# MAX31865.net
KiCad netlist of a schematic drawn in EAGLE
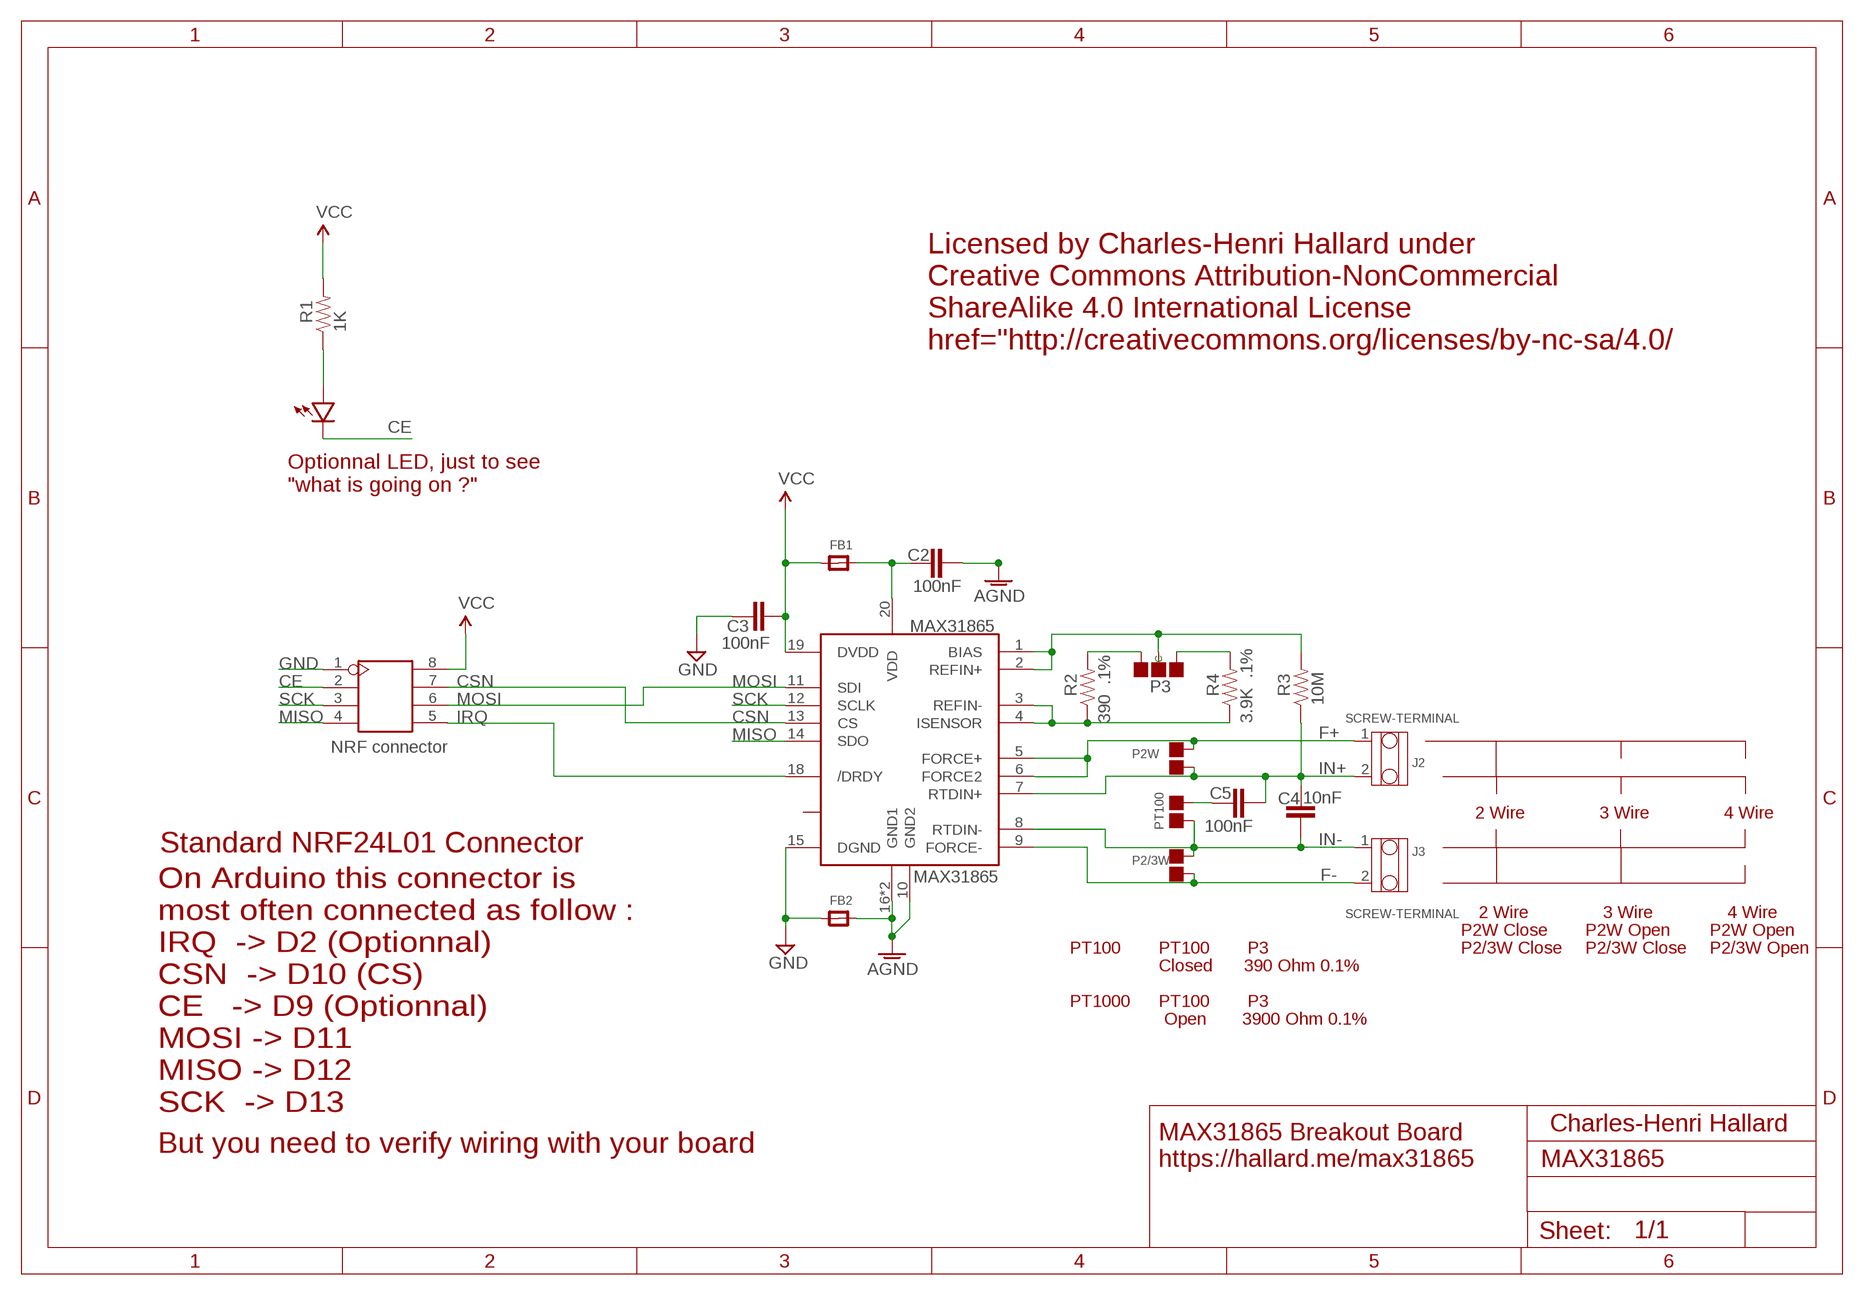
[diagram p0: schematic, sheet 1]

(export (version "E")
  (design (tool "Eeschema 10.0.6"))
  (components
    (comp (ref "C2")
      (value "100nF")
      (footprint "eagle-import:0603-CAP")
      (libsource (lib "eagle-import") (part "CAP0603-CAP"))
    )
    (comp (ref "C3")
      (value "100nF")
      (footprint "eagle-import:0603-CAP")
      (libsource (lib "eagle-import") (part "CAP0603-CAP"))
    )
    (comp (ref "C4")
      (value "10nF")
      (footprint "eagle-import:0603-CAP")
      (libsource (lib "eagle-import") (part "CAP0603-CAP"))
    )
    (comp (ref "C5")
      (value "100nF")
      (footprint "eagle-import:0603-CAP")
      (libsource (lib "eagle-import") (part "CAP0603-CAP"))
    )
    (comp (ref "FB1")
      (value "FERRITE_0603MP")
      (footprint "eagle-import:_0603MP")
      (libsource (lib "eagle-import") (part "FERRITE_0603MP"))
    )
    (comp (ref "FB2")
      (value "FERRITE_0603MP")
      (footprint "eagle-import:_0603MP")
      (libsource (lib "eagle-import") (part "FERRITE_0603MP"))
    )
    (comp (ref "J1")
      (value "NRF connector")
      (footprint "eagle-import:2X4P-2.54")
      (libsource (lib "eagle-import") (part "HEADER-2X4P-2.54"))
    )
    (comp (ref "J2")
      (value "SCREW-TERMINAL")
      (footprint "eagle-import:2P-3.5")
      (libsource (lib "eagle-import") (part "SCREW-TERMINAL-2P-3470070P1"))
    )
    (comp (ref "J3")
      (value "SCREW-TERMINAL")
      (footprint "eagle-import:2P-3.5")
      (libsource (lib "eagle-import") (part "SCREW-TERMINAL-2P-3470070P1"))
    )
    (comp (ref "MAX31865")
      (value "MAX31865")
      (footprint "eagle-import:TQFN20-5X5")
      (libsource (lib "eagle-import") (part "MAX31865"))
    )
    (comp (ref "P2/3W")
      (value "4 Wire")
      (footprint "eagle-import:2P-SMD-1.78X1.27")
      (fields (field (name "PARTNO") "DNP"))
      (libsource (lib "eagle-import") (part "PAD-JUMPER-2P"))
    )
    (comp (ref "P2W")
      (value "3 Wire")
      (footprint "eagle-import:2P-SMD-1.78X1.27")
      (fields (field (name "PARTNO") "DNP"))
      (libsource (lib "eagle-import") (part "PAD-JUMPER-2P"))
    )
    (comp (ref "P3")
      (value "PAD-JUMPER-3P-40*40")
      (footprint "eagle-import:3P-SMD-4.1X1.5")
      (fields (field (name "PARTNO") "DNP"))
      (libsource (lib "eagle-import") (part "PAD-JUMPER-3P-4040"))
    )
    (comp (ref "PT100")
      (value "PAD-JUMPER-2P")
      (footprint "eagle-import:2P-SMD-1.78X1.27")
      (fields (field (name "PARTNO") "DNP"))
      (libsource (lib "eagle-import") (part "PAD-JUMPER-2P"))
    )
    (comp (ref "R1")
      (value "1K")
      (footprint "eagle-import:0603-RES")
      (libsource (lib "eagle-import") (part "RESISTOR0603-RES"))
    )
    (comp (ref "R2")
      (value "390 .1%")
      (footprint "eagle-import:0805-RES")
      (libsource (lib "eagle-import") (part "RESISTOR0805-RES"))
    )
    (comp (ref "R3")
      (value "10M")
      (footprint "eagle-import:0603-RES")
      (libsource (lib "eagle-import") (part "RESISTOR0603-RES"))
    )
    (comp (ref "R4")
      (value "3.9K .1%")
      (footprint "eagle-import:0805-RES")
      (libsource (lib "eagle-import") (part "RESISTOR0805-RES"))
    )
    (comp (ref "U$1")
      (value "LED0805-LARGE")
      (footprint "eagle-import:0805-LED-LARGEPADS")
      (libsource (lib "eagle-import") (part "LED0805-LARGE"))
    )
  )
  (nets
    (net (code "1") (name "/CE") (class "Default")
      (node (ref "J1") (pin "2") (pinfunction "2_2") (pintype "bidirectional"))
      (node (ref "U$1") (pin "MINUS") (pinfunction "MINUS_MINUS") (pintype "passive"))
    )
    (net (code "2") (name "/CSN") (class "Default")
      (node (ref "J1") (pin "7") (pinfunction "7_7") (pintype "bidirectional"))
      (node (ref "MAX31865") (pin "13") (pinfunction "CS_13") (pintype "bidirectional"))
    )
    (net (code "3") (name "/F+") (class "Default")
      (node (ref "J2") (pin "1") (pinfunction "1_1") (pintype "bidirectional"))
      (node (ref "MAX31865") (pin "5") (pinfunction "FORCE+_5") (pintype "bidirectional"))
      (node (ref "MAX31865") (pin "6") (pinfunction "FORCE2_6") (pintype "bidirectional"))
      (node (ref "P2W") (pin "2") (pinfunction "2_2") (pintype "bidirectional"))
    )
    (net (code "4") (name "/F-") (class "Default")
      (node (ref "J3") (pin "2") (pinfunction "2_2") (pintype "bidirectional"))
      (node (ref "MAX31865") (pin "9") (pinfunction "FORCE-_9") (pintype "bidirectional"))
      (node (ref "P2/3W") (pin "1") (pinfunction "1_1") (pintype "bidirectional"))
    )
    (net (code "5") (name "/IN+") (class "Default")
      (node (ref "C4") (pin "1") (pinfunction "1_1") (pintype "passive"))
      (node (ref "C5") (pin "2") (pinfunction "2_2") (pintype "passive"))
      (node (ref "J2") (pin "2") (pinfunction "2_2") (pintype "bidirectional"))
      (node (ref "MAX31865") (pin "7") (pinfunction "RTDIN+_7") (pintype "bidirectional"))
      (node (ref "P2W") (pin "1") (pinfunction "1_1") (pintype "bidirectional"))
      (node (ref "R3") (pin "1") (pinfunction "1_1") (pintype "passive"))
    )
    (net (code "6") (name "/IN-") (class "Default")
      (node (ref "C4") (pin "2") (pinfunction "2_2") (pintype "passive"))
      (node (ref "J3") (pin "1") (pinfunction "1_1") (pintype "bidirectional"))
      (node (ref "MAX31865") (pin "8") (pinfunction "RTDIN-_8") (pintype "bidirectional"))
      (node (ref "P2/3W") (pin "2") (pinfunction "2_2") (pintype "bidirectional"))
      (node (ref "PT100") (pin "1") (pinfunction "1_1") (pintype "bidirectional"))
    )
    (net (code "7") (name "/IRQ") (class "Default")
      (node (ref "J1") (pin "5") (pinfunction "5_5") (pintype "bidirectional"))
      (node (ref "MAX31865") (pin "18") (pinfunction "/DRDY_18") (pintype "input"))
    )
    (net (code "8") (name "/MISO") (class "Default")
      (node (ref "J1") (pin "4") (pinfunction "4_4") (pintype "bidirectional"))
      (node (ref "MAX31865") (pin "14") (pinfunction "SDO_14") (pintype "bidirectional"))
    )
    (net (code "9") (name "/MOSI") (class "Default")
      (node (ref "J1") (pin "6") (pinfunction "6_6") (pintype "bidirectional"))
      (node (ref "MAX31865") (pin "11") (pinfunction "SDI_11") (pintype "bidirectional"))
    )
    (net (code "10") (name "/SCK") (class "Default")
      (node (ref "J1") (pin "3") (pinfunction "3_3") (pintype "bidirectional"))
      (node (ref "MAX31865") (pin "12") (pinfunction "SCLK_12") (pintype "bidirectional"))
    )
    (net (code "11") (name "AGND") (class "Default")
      (node (ref "C2") (pin "2") (pinfunction "2_2") (pintype "passive"))
      (node (ref "FB2") (pin "2") (pinfunction "P$2_2") (pintype "passive"))
      (node (ref "MAX31865") (pin "10") (pinfunction "GND2_10") (pintype "bidirectional"))
      (node (ref "MAX31865") (pin "16") (pinfunction "GND1_16") (pintype "bidirectional"))
      (node (ref "MAX31865") (pin "EXP") (pinfunction "GND1_EXP") (pintype "bidirectional"))
    )
    (net (code "12") (name "GND") (class "Default")
      (node (ref "C3") (pin "2") (pinfunction "2_2") (pintype "passive"))
      (node (ref "FB2") (pin "1") (pinfunction "P$1_1") (pintype "passive"))
      (node (ref "J1") (pin "1") (pinfunction "1_1") (pintype "bidirectional"))
      (node (ref "MAX31865") (pin "15") (pinfunction "DGND_15") (pintype "bidirectional"))
    )
    (net (code "13") (name "Net-(C5-Pad1)") (class "Default")
      (node (ref "C5") (pin "1") (pinfunction "1_1") (pintype "passive"))
      (node (ref "PT100") (pin "2") (pinfunction "2_2") (pintype "bidirectional"))
    )
    (net (code "14") (name "Net-(FB1-P$2)") (class "Default")
      (node (ref "C2") (pin "1") (pinfunction "1_1") (pintype "passive"))
      (node (ref "FB1") (pin "2") (pinfunction "P$2_2") (pintype "passive"))
      (node (ref "MAX31865") (pin "20") (pinfunction "VDD_20") (pintype "power_in"))
    )
    (net (code "15") (name "Net-(MAX31865-BIAS)") (class "Default")
      (node (ref "MAX31865") (pin "1") (pinfunction "BIAS_1") (pintype "bidirectional"))
      (node (ref "MAX31865") (pin "2") (pinfunction "REFIN+_2") (pintype "bidirectional"))
      (node (ref "P3") (pin "MM") (pinfunction "C_MM") (pintype "bidirectional"))
      (node (ref "R3") (pin "2") (pinfunction "2_2") (pintype "passive"))
    )
    (net (code "16") (name "Net-(MAX31865-ISENSOR)") (class "Default")
      (node (ref "MAX31865") (pin "3") (pinfunction "REFIN-_3") (pintype "bidirectional"))
      (node (ref "MAX31865") (pin "4") (pinfunction "ISENSOR_4") (pintype "bidirectional"))
      (node (ref "R2") (pin "1") (pinfunction "1_1") (pintype "passive"))
      (node (ref "R4") (pin "1") (pinfunction "1_1") (pintype "passive"))
    )
    (net (code "17") (name "Net-(P3-L)") (class "Default")
      (node (ref "P3") (pin "00") (pinfunction "L_00") (pintype "bidirectional"))
      (node (ref "R4") (pin "2") (pinfunction "2_2") (pintype "passive"))
    )
    (net (code "18") (name "Net-(P3-R)") (class "Default")
      (node (ref "P3") (pin "11") (pinfunction "R_11") (pintype "bidirectional"))
      (node (ref "R2") (pin "2") (pinfunction "2_2") (pintype "passive"))
    )
    (net (code "19") (name "Net-(R1-Pad1)") (class "Default")
      (node (ref "R1") (pin "1") (pinfunction "1_1") (pintype "passive"))
      (node (ref "U$1") (pin "PLUS") (pinfunction "PLUS_PLUS") (pintype "passive"))
    )
    (net (code "20") (name "VCC") (class "Default")
      (node (ref "C3") (pin "1") (pinfunction "1_1") (pintype "passive"))
      (node (ref "FB1") (pin "1") (pinfunction "P$1_1") (pintype "passive"))
      (node (ref "J1") (pin "8") (pinfunction "8_8") (pintype "bidirectional"))
      (node (ref "MAX31865") (pin "19") (pinfunction "DVDD_19") (pintype "power_in"))
      (node (ref "R1") (pin "2") (pinfunction "2_2") (pintype "passive"))
    )
    (net (code "21") (name "unconnected-(MAX31865-NC-Pad17)") (class "Default")
      (node (ref "MAX31865") (pin "17") (pinfunction "NC_17") (pintype "bidirectional"))
    )
  )
)
